# PAYL0008_GMSK_Prototyping_Board.net
KiCad netlist of a schematic drawn in Altium Designer
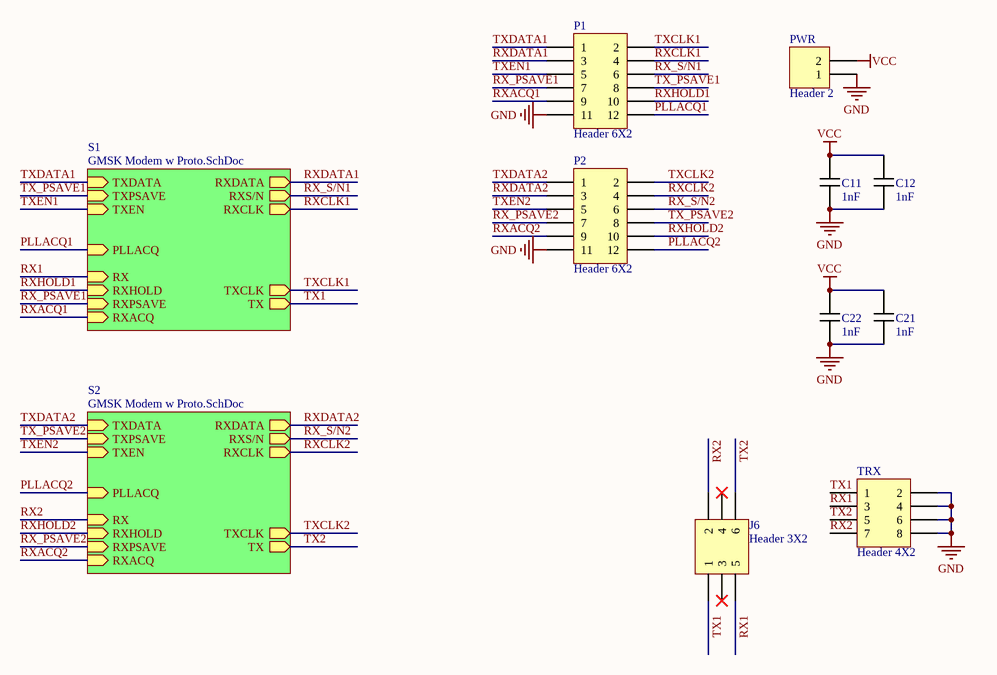
[diagram p0: PAYL0008 GMSK Prototyping Board.SchDoc]

(export (version "E")
  (design (tool "Eeschema 10.0.6"))
  (components
    (comp (ref "C11")
      (value "1nF")
      (footprint "0805 Cap")
      (description "0805 MLCC - X7R, 10%")
      (fields (field (name "Comment") "0805 Cap"))
      (libsource (lib "GMSK Prototyping Board") (part "0805 MLCC - X7R, 10%"))
    )
    (comp (ref "C12")
      (value "1nF")
      (footprint "0805 Cap")
      (description "0805 MLCC - X7R, 10%")
      (fields (field (name "Comment") "0805 Cap"))
      (libsource (lib "GMSK Prototyping Board") (part "0805 MLCC - X7R, 10%"))
    )
    (comp (ref "C21")
      (value "1nF")
      (footprint "0805 Cap")
      (description "0805 MLCC - X7R, 10%")
      (fields (field (name "Comment") "0805 Cap"))
      (libsource (lib "GMSK Prototyping Board") (part "0805 MLCC - X7R, 10%"))
    )
    (comp (ref "C22")
      (value "1nF")
      (footprint "0805 Cap")
      (description "0805 MLCC - X7R, 10%")
      (fields (field (name "Comment") "0805 Cap"))
      (libsource (lib "GMSK Prototyping Board") (part "0805 MLCC - X7R, 10%"))
    )
    (comp (ref "J6")
      (value "Header 3X2")
      (footprint "HDR2X3")
      (description "Header, 3-Pin, Dual row")
      (fields (field (name "PUBLISHER") "Altium Limited"))
      (libsource (lib "GMSK Prototyping Board") (part "Header 3X2"))
    )
    (comp (ref "P1")
      (value "Header 6X2")
      (footprint "HDR2X6")
      (description "Header, 6-Pin, Dual row")
      (fields (field (name "PUBLISHER") "Altium Limited"))
      (libsource (lib "GMSK Prototyping Board") (part "Header 6X2"))
    )
    (comp (ref "P2")
      (value "Header 6X2")
      (footprint "HDR2X6")
      (description "Header, 6-Pin, Dual row")
      (fields (field (name "PUBLISHER") "Altium Limited"))
      (libsource (lib "GMSK Prototyping Board") (part "Header 6X2"))
    )
    (comp (ref "PWR")
      (value "Header 2")
      (footprint "HDR1X2")
      (description "Header, 2-Pin")
      (fields (field (name "PUBLISHER") "Altium Limited"))
      (libsource (lib "GMSK Prototyping Board") (part "Header 2"))
    )
    (comp (ref "TRX")
      (value "Header 4X2")
      (footprint "HDR2X4")
      (description "Header, 4-Pin, Dual row")
      (fields (field (name "PUBLISHER") "Altium Limited"))
      (libsource (lib "GMSK Prototyping Board") (part "Header 4X2"))
    )
  )
  (nets
    (net (code "1") (name "/PLLACQ1") (class "Default")
      (node (ref "P1") (pin "12") (pinfunction "12_12") (pintype "passive"))
    )
    (net (code "2") (name "/PLLACQ2") (class "Default")
      (node (ref "P2") (pin "12") (pinfunction "12_12") (pintype "passive"))
    )
    (net (code "3") (name "/RX1") (class "Default")
      (node (ref "J6") (pin "5") (pinfunction "5_5") (pintype "passive"))
      (node (ref "TRX") (pin "3") (pinfunction "3_3") (pintype "passive"))
    )
    (net (code "4") (name "/RX2") (class "Default")
      (node (ref "J6") (pin "2") (pinfunction "2_2") (pintype "passive"))
      (node (ref "TRX") (pin "7") (pinfunction "7_7") (pintype "passive"))
    )
    (net (code "5") (name "/RXACQ1") (class "Default")
      (node (ref "P1") (pin "9") (pinfunction "9_9") (pintype "passive"))
    )
    (net (code "6") (name "/RXACQ2") (class "Default")
      (node (ref "P2") (pin "9") (pinfunction "9_9") (pintype "passive"))
    )
    (net (code "7") (name "/RXCLK1") (class "Default")
      (node (ref "P1") (pin "4") (pinfunction "4_4") (pintype "passive"))
    )
    (net (code "8") (name "/RXCLK2") (class "Default")
      (node (ref "P2") (pin "4") (pinfunction "4_4") (pintype "passive"))
    )
    (net (code "9") (name "/RXDATA1") (class "Default")
      (node (ref "P1") (pin "3") (pinfunction "3_3") (pintype "passive"))
    )
    (net (code "10") (name "/RXDATA2") (class "Default")
      (node (ref "P2") (pin "3") (pinfunction "3_3") (pintype "passive"))
    )
    (net (code "11") (name "/RXHOLD1") (class "Default")
      (node (ref "P1") (pin "10") (pinfunction "10_10") (pintype "passive"))
    )
    (net (code "12") (name "/RXHOLD2") (class "Default")
      (node (ref "P2") (pin "10") (pinfunction "10_10") (pintype "passive"))
    )
    (net (code "13") (name "/RX_PSAVE1") (class "Default")
      (node (ref "P1") (pin "7") (pinfunction "7_7") (pintype "passive"))
    )
    (net (code "14") (name "/RX_PSAVE2") (class "Default")
      (node (ref "P2") (pin "7") (pinfunction "7_7") (pintype "passive"))
    )
    (net (code "15") (name "/RX_S{slash}N1") (class "Default")
      (node (ref "P1") (pin "6") (pinfunction "6_6") (pintype "passive"))
    )
    (net (code "16") (name "/RX_S{slash}N2") (class "Default")
      (node (ref "P2") (pin "6") (pinfunction "6_6") (pintype "passive"))
    )
    (net (code "17") (name "/TX1") (class "Default")
      (node (ref "J6") (pin "1") (pinfunction "1_1") (pintype "passive"))
      (node (ref "TRX") (pin "1") (pinfunction "1_1") (pintype "passive"))
    )
    (net (code "18") (name "/TX2") (class "Default")
      (node (ref "J6") (pin "6") (pinfunction "6_6") (pintype "passive"))
      (node (ref "TRX") (pin "5") (pinfunction "5_5") (pintype "passive"))
    )
    (net (code "19") (name "/TXCLK1") (class "Default")
      (node (ref "P1") (pin "2") (pinfunction "2_2") (pintype "passive"))
    )
    (net (code "20") (name "/TXCLK2") (class "Default")
      (node (ref "P2") (pin "2") (pinfunction "2_2") (pintype "passive"))
    )
    (net (code "21") (name "/TXDATA1") (class "Default")
      (node (ref "P1") (pin "1") (pinfunction "1_1") (pintype "passive"))
    )
    (net (code "22") (name "/TXDATA2") (class "Default")
      (node (ref "P2") (pin "1") (pinfunction "1_1") (pintype "passive"))
    )
    (net (code "23") (name "/TXEN1") (class "Default")
      (node (ref "P1") (pin "5") (pinfunction "5_5") (pintype "passive"))
    )
    (net (code "24") (name "/TXEN2") (class "Default")
      (node (ref "P2") (pin "5") (pinfunction "5_5") (pintype "passive"))
    )
    (net (code "25") (name "/TX_PSAVE1") (class "Default")
      (node (ref "P1") (pin "8") (pinfunction "8_8") (pintype "passive"))
    )
    (net (code "26") (name "/TX_PSAVE2") (class "Default")
      (node (ref "P2") (pin "8") (pinfunction "8_8") (pintype "passive"))
    )
    (net (code "27") (name "GND") (class "Default")
      (node (ref "C11") (pin "2") (pinfunction "2_2") (pintype "passive"))
      (node (ref "C12") (pin "2") (pinfunction "2_2") (pintype "passive"))
      (node (ref "C21") (pin "1") (pinfunction "1_1") (pintype "passive"))
      (node (ref "C22") (pin "1") (pinfunction "1_1") (pintype "passive"))
      (node (ref "P1") (pin "11") (pinfunction "11_11") (pintype "passive"))
      (node (ref "P2") (pin "11") (pinfunction "11_11") (pintype "passive"))
      (node (ref "PWR") (pin "1") (pinfunction "1_1") (pintype "passive"))
      (node (ref "TRX") (pin "2") (pinfunction "2_2") (pintype "passive"))
      (node (ref "TRX") (pin "4") (pinfunction "4_4") (pintype "passive"))
      (node (ref "TRX") (pin "6") (pinfunction "6_6") (pintype "passive"))
      (node (ref "TRX") (pin "8") (pinfunction "8_8") (pintype "passive"))
    )
    (net (code "28") (name "VCC") (class "Default")
      (node (ref "C11") (pin "1") (pinfunction "1_1") (pintype "passive"))
      (node (ref "C12") (pin "1") (pinfunction "1_1") (pintype "passive"))
      (node (ref "C21") (pin "2") (pinfunction "2_2") (pintype "passive"))
      (node (ref "C22") (pin "2") (pinfunction "2_2") (pintype "passive"))
      (node (ref "PWR") (pin "2") (pinfunction "2_2") (pintype "passive"))
    )
    (net (code "29") (name "unconnected-(J6-Pad3)") (class "Default")
      (node (ref "J6") (pin "3") (pinfunction "3_3") (pintype "passive+no_connect"))
    )
    (net (code "30") (name "unconnected-(J6-Pad4)") (class "Default")
      (node (ref "J6") (pin "4") (pinfunction "4_4") (pintype "passive+no_connect"))
    )
  )
)
